# LEDS_AND_DRIVER.net
KiCad netlist of a schematic drawn in Altium Designer
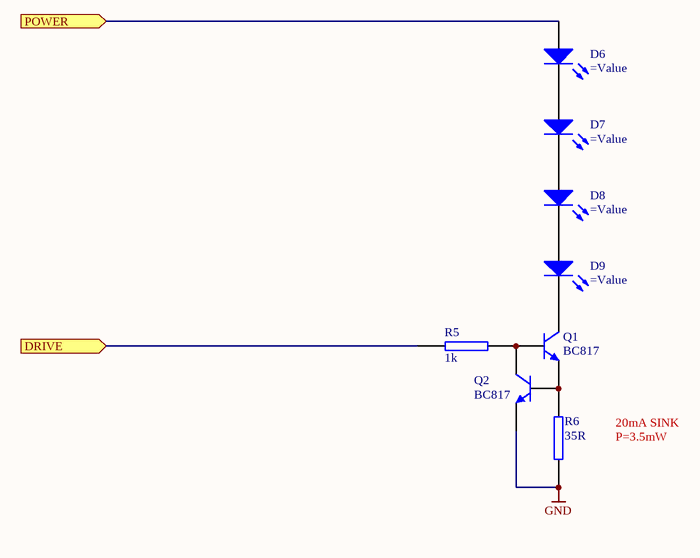
[diagram p0: LEDS AND DRIVER.SchDoc]

(export (version "E")
  (design (tool "Eeschema 10.0.6"))
  (components
    (comp (ref "D6")
      (value "~")
      (footprint "LED SUPERFLUX AMBER")
      (description "LED 55")
      (libsource (lib "NASCO") (part "LED 3mm RED"))
    )
    (comp (ref "D7")
      (value "~")
      (footprint "LED SUPERFLUX AMBER")
      (description "LED 55")
      (libsource (lib "NASCO") (part "LED 3mm RED"))
    )
    (comp (ref "D8")
      (value "~")
      (footprint "LED SUPERFLUX AMBER")
      (description "LED 55")
      (libsource (lib "NASCO") (part "LED 3mm RED"))
    )
    (comp (ref "D9")
      (value "~")
      (footprint "LED SUPERFLUX AMBER")
      (description "LED 55")
      (libsource (lib "NASCO") (part "LED 3mm RED"))
    )
    (comp (ref "Q1")
      (value "BC817")
      (footprint "SOT23-3L")
      (description "NPN Bipolar Transistor")
      (fields
        (field (name "MANUFACTURER") "ON Semiconductor")
        (field (name "MOUSER PART NO.") "863-BC817-25LT1G")
      )
      (libsource (lib "NASCO") (part "BC817"))
    )
    (comp (ref "Q2")
      (value "BC817")
      (footprint "SOT23-3L")
      (description "NPN Bipolar Transistor")
      (fields
        (field (name "MANUFACTURER") "ON Semiconductor")
        (field (name "MOUSER PART NO.") "863-BC817-25LT1G")
      )
      (libsource (lib "NASCO") (part "BC817"))
    )
    (comp (ref "R5")
      (value "1k")
      (footprint "RES (3D) - 0805")
      (description "RESISTOR SMD 0603 1k")
      (libsource (lib "NASCO Resistors") (part "RES SMD 0603 1k"))
    )
    (comp (ref "R6")
      (value "35R")
      (footprint "RES (3D) - 0805")
      (description "RESISTOR SMD 0603 1k")
      (libsource (lib "NASCO Resistors") (part "RES SMD 0603 1k"))
    )
  )
  (nets
    (net (code "1") (name "/DRIVE") (class "Default")
      (node (ref "R5") (pin "2") (pinfunction "2_2") (pintype "passive"))
    )
    (net (code "2") (name "/POWER") (class "Default")
      (node (ref "D6") (pin "1") (pinfunction "A_1") (pintype "passive"))
    )
    (net (code "3") (name "GND") (class "Default")
      (node (ref "Q2") (pin "2") (pinfunction "E_2") (pintype "passive"))
      (node (ref "R6") (pin "1") (pinfunction "1_1") (pintype "passive"))
    )
    (net (code "4") (name "Net-(D6-K)") (class "Default")
      (node (ref "D6") (pin "2") (pinfunction "K_2") (pintype "passive"))
      (node (ref "D7") (pin "1") (pinfunction "A_1") (pintype "passive"))
    )
    (net (code "5") (name "Net-(D7-K)") (class "Default")
      (node (ref "D7") (pin "2") (pinfunction "K_2") (pintype "passive"))
      (node (ref "D8") (pin "1") (pinfunction "A_1") (pintype "passive"))
    )
    (net (code "6") (name "Net-(D8-K)") (class "Default")
      (node (ref "D8") (pin "2") (pinfunction "K_2") (pintype "passive"))
      (node (ref "D9") (pin "1") (pinfunction "A_1") (pintype "passive"))
    )
    (net (code "7") (name "Net-(D9-K)") (class "Default")
      (node (ref "D9") (pin "2") (pinfunction "K_2") (pintype "passive"))
      (node (ref "Q1") (pin "3") (pinfunction "C_3") (pintype "passive"))
    )
    (net (code "8") (name "Net-(Q1-B)") (class "Default")
      (node (ref "Q1") (pin "1") (pinfunction "B_1") (pintype "passive"))
      (node (ref "Q2") (pin "3") (pinfunction "C_3") (pintype "passive"))
      (node (ref "R5") (pin "1") (pinfunction "1_1") (pintype "passive"))
    )
    (net (code "9") (name "Net-(Q1-E)") (class "Default")
      (node (ref "Q1") (pin "2") (pinfunction "E_2") (pintype "passive"))
      (node (ref "Q2") (pin "1") (pinfunction "B_1") (pintype "passive"))
      (node (ref "R6") (pin "2") (pinfunction "2_2") (pintype "passive"))
    )
  )
)
